# drone3.net
KiCad netlist of a schematic drawn in EAGLE
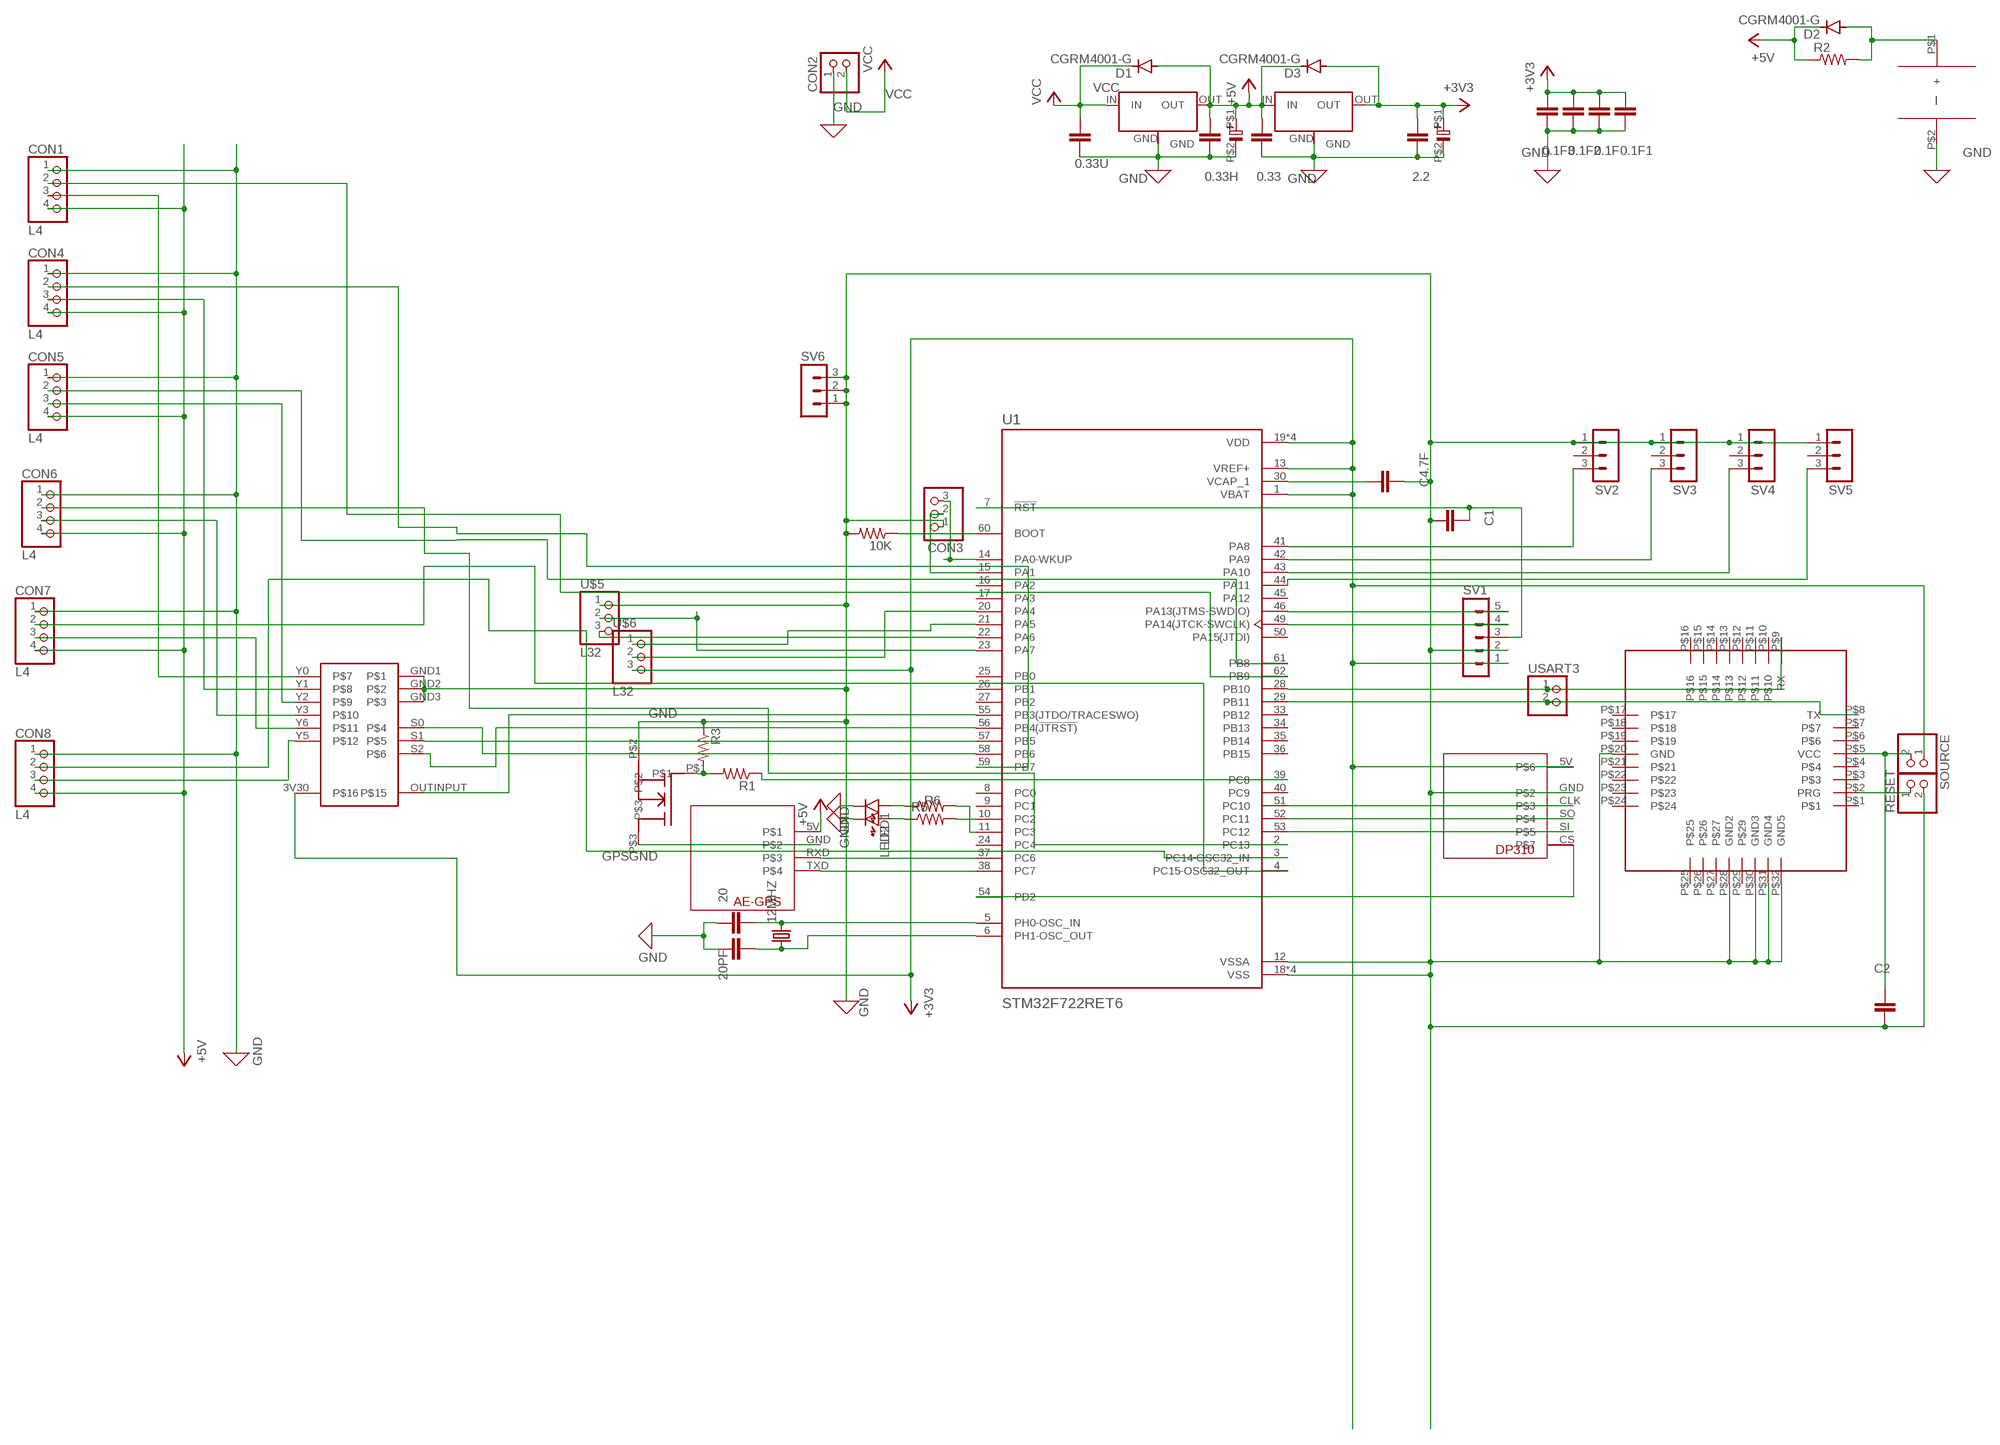
[diagram p0: schematic, sheet 1]

(export (version "E")
  (design (tool "Eeschema 10.0.6"))
  (components
    (comp (ref "0.1F")
      (value "C-EUC0603")
      (footprint "eagle-import:C0603")
      (libsource (lib "eagle-import") (part "C-EUC0603"))
    )
    (comp (ref "0.1F1")
      (value "C-EUC0603")
      (footprint "eagle-import:C0603")
      (libsource (lib "eagle-import") (part "C-EUC0603"))
    )
    (comp (ref "0.1F2")
      (value "C-EUC0603")
      (footprint "eagle-import:C0603")
      (libsource (lib "eagle-import") (part "C-EUC0603"))
    )
    (comp (ref "0.1F3")
      (value "C-EUC0603")
      (footprint "eagle-import:C0603")
      (libsource (lib "eagle-import") (part "C-EUC0603"))
    )
    (comp (ref "0.33")
      (value "C-EUC0603")
      (footprint "eagle-import:C0603")
      (libsource (lib "eagle-import") (part "C-EUC0603"))
    )
    (comp (ref "0.33H")
      (value "C-EUC0603")
      (footprint "eagle-import:C0603")
      (libsource (lib "eagle-import") (part "C-EUC0603"))
    )
    (comp (ref "0.33U")
      (value "C-EUC0603")
      (footprint "eagle-import:C0603")
      (libsource (lib "eagle-import") (part "C-EUC0603"))
    )
    (comp (ref "2.2")
      (value "C-EUC0603")
      (footprint "eagle-import:C0603")
      (libsource (lib "eagle-import") (part "C-EUC0603"))
    )
    (comp (ref "10K")
      (value "R-US_R0603")
      (footprint "eagle-import:R0603")
      (libsource (lib "eagle-import") (part "R-US_R0603"))
    )
    (comp (ref "12MHZ")
      (value "CRYSTALHC49S")
      (footprint "eagle-import:HC49_S")
      (fields (field (name "SPICEPREFIX") "B"))
      (libsource (lib "eagle-import") (part "CRYSTALHC49S"))
    )
    (comp (ref "20")
      (value "C-EUC0603")
      (footprint "eagle-import:C0603")
      (libsource (lib "eagle-import") (part "C-EUC0603"))
    )
    (comp (ref "20PF")
      (value "C-EUC0603")
      (footprint "eagle-import:C0603")
      (libsource (lib "eagle-import") (part "C-EUC0603"))
    )
    (comp (ref "47")
      (value "UCD0J470MCL1GS")
      (footprint "eagle-import:UCD0J470MCL1GS")
      (libsource (lib "eagle-import") (part "UCD0J470MCL1GS"))
    )
    (comp (ref "47U")
      (value "UCD0J470MCL1GS")
      (footprint "eagle-import:UCD0J470MCL1GS")
      (libsource (lib "eagle-import") (part "UCD0J470MCL1GS"))
    )
    (comp (ref "C1")
      (value "C-EUC0603")
      (footprint "eagle-import:C0603")
      (libsource (lib "eagle-import") (part "C-EUC0603"))
    )
    (comp (ref "C2")
      (value "C-EUC0603")
      (footprint "eagle-import:C0603")
      (libsource (lib "eagle-import") (part "C-EUC0603"))
    )
    (comp (ref "C4.7F")
      (value "C-EUC0603")
      (footprint "eagle-import:C0603")
      (libsource (lib "eagle-import") (part "C-EUC0603"))
    )
    (comp (ref "CON1")
      (value "L4")
      (footprint "eagle-import:L_4")
      (libsource (lib "eagle-import") (part "L4"))
    )
    (comp (ref "CON2")
      (value "L2")
      (footprint "eagle-import:L_2")
      (libsource (lib "eagle-import") (part "L2"))
    )
    (comp (ref "CON3")
      (value "L3")
      (footprint "eagle-import:L_3")
      (libsource (lib "eagle-import") (part "L3"))
    )
    (comp (ref "CON4")
      (value "L4")
      (footprint "eagle-import:L_4")
      (libsource (lib "eagle-import") (part "L4"))
    )
    (comp (ref "CON5")
      (value "L4")
      (footprint "eagle-import:L_4")
      (libsource (lib "eagle-import") (part "L4"))
    )
    (comp (ref "CON6")
      (value "L4")
      (footprint "eagle-import:L_4")
      (libsource (lib "eagle-import") (part "L4"))
    )
    (comp (ref "CON7")
      (value "L4")
      (footprint "eagle-import:L_4")
      (libsource (lib "eagle-import") (part "L4"))
    )
    (comp (ref "CON8")
      (value "L4")
      (footprint "eagle-import:L_4")
      (libsource (lib "eagle-import") (part "L4"))
    )
    (comp (ref "CS1")
      (value "DP310DP310")
      (footprint "eagle-import:AE-GPS-HOLE")
      (libsource (lib "eagle-import") (part "DP310DP310"))
    )
    (comp (ref "D1")
      (value "CGRM4001-G")
      (footprint "eagle-import:SOD-123_MINI-SMA")
      (libsource (lib "eagle-import") (part "CGRM400-G1"))
    )
    (comp (ref "D2")
      (value "CGRM4001-G")
      (footprint "eagle-import:SOD-123_MINI-SMA")
      (libsource (lib "eagle-import") (part "CGRM400-G1"))
    )
    (comp (ref "D3")
      (value "CGRM4001-G")
      (footprint "eagle-import:SOD-123_MINI-SMA")
      (libsource (lib "eagle-import") (part "CGRM400-G1"))
    )
    (comp (ref "LED1")
      (value "LED1608")
      (footprint "eagle-import:LED1608")
      (libsource (lib "eagle-import") (part "LED1608"))
    )
    (comp (ref "LED2")
      (value "LED1608")
      (footprint "eagle-import:LED1608")
      (libsource (lib "eagle-import") (part "LED1608"))
    )
    (comp (ref "OUTPUT")
      (value "MULTI")
      (footprint "eagle-import:MULTI")
      (libsource (lib "eagle-import") (part "MULTI"))
    )
    (comp (ref "R1")
      (value "R-US_R0603")
      (footprint "eagle-import:R0603")
      (libsource (lib "eagle-import") (part "R-US_R0603"))
    )
    (comp (ref "R2")
      (value "R-US_0207/7")
      (footprint "eagle-import:0207_7")
      (libsource (lib "eagle-import") (part "R-US_0207/7"))
    )
    (comp (ref "R3")
      (value "R-US_R0603")
      (footprint "eagle-import:R0603")
      (libsource (lib "eagle-import") (part "R-US_R0603"))
    )
    (comp (ref "R5")
      (value "R-US_R0603")
      (footprint "eagle-import:R0603")
      (libsource (lib "eagle-import") (part "R-US_R0603"))
    )
    (comp (ref "R6")
      (value "R-US_R0603")
      (footprint "eagle-import:R0603")
      (libsource (lib "eagle-import") (part "R-US_R0603"))
    )
    (comp (ref "RESET")
      (value "PINHD-1X2")
      (footprint "eagle-import:1X02")
      (libsource (lib "eagle-import") (part "PINHD-1X2"))
    )
    (comp (ref "SOURCE")
      (value "PINHD-1X2")
      (footprint "eagle-import:1X02")
      (libsource (lib "eagle-import") (part "PINHD-1X2"))
    )
    (comp (ref "SV1")
      (value "MA05-1")
      (footprint "eagle-import:MA05-1")
      (libsource (lib "eagle-import") (part "MA05-1"))
    )
    (comp (ref "SV2")
      (value "MA03-1")
      (footprint "eagle-import:MA03-1")
      (libsource (lib "eagle-import") (part "MA03-1"))
    )
    (comp (ref "SV3")
      (value "MA03-1")
      (footprint "eagle-import:MA03-1")
      (libsource (lib "eagle-import") (part "MA03-1"))
    )
    (comp (ref "SV4")
      (value "MA03-1")
      (footprint "eagle-import:MA03-1")
      (libsource (lib "eagle-import") (part "MA03-1"))
    )
    (comp (ref "SV5")
      (value "MA03-1")
      (footprint "eagle-import:MA03-1")
      (libsource (lib "eagle-import") (part "MA03-1"))
    )
    (comp (ref "SV6")
      (value "MA03-1")
      (footprint "eagle-import:MA03-1")
      (libsource (lib "eagle-import") (part "MA03-1"))
    )
    (comp (ref "U$1")
      (value "LITE")
      (footprint "eagle-import:LITE")
      (libsource (lib "eagle-import") (part "LITE"))
    )
    (comp (ref "U$3")
      (value "AE-GPS-HOLE")
      (footprint "eagle-import:AE-GPS-HOLE")
      (libsource (lib "eagle-import") (part "AE-GPS-HOLE"))
    )
    (comp (ref "U$4")
      (value "NJM2391DL1-33")
      (footprint "eagle-import:NJM2391DL1-33")
      (libsource (lib "eagle-import") (part "NJM2391DL1-33"))
    )
    (comp (ref "U$5")
      (value "L32")
      (footprint "eagle-import:L_32")
      (libsource (lib "eagle-import") (part "L32"))
    )
    (comp (ref "U$6")
      (value "L32")
      (footprint "eagle-import:L_32")
      (libsource (lib "eagle-import") (part "L32"))
    )
    (comp (ref "U$7")
      (value "SSM3K329R")
      (footprint "eagle-import:SSM3K329R")
      (libsource (lib "eagle-import") (part "SSM3K329R"))
    )
    (comp (ref "U$8")
      (value "VEC5R4355QG-I")
      (footprint "eagle-import:VEC5R4355QG-I")
      (libsource (lib "eagle-import") (part "VEC5R4355QG-I"))
    )
    (comp (ref "U$9")
      (value "NJM2391DL1-33")
      (footprint "eagle-import:NJM2391DL1-33")
      (libsource (lib "eagle-import") (part "NJM2391DL1-33"))
    )
    (comp (ref "U1")
      (value "STM32F722RET6")
      (footprint "eagle-import:QFP50P1200X1200X160-64N")
      (fields (field (name "MF") "STMicroelectronics"))
      (libsource (lib "eagle-import") (part "STM32F722RET6"))
    )
    (comp (ref "USART3")
      (value "PINHD-1X2")
      (footprint "eagle-import:1X02")
      (libsource (lib "eagle-import") (part "PINHD-1X2"))
    )
  )
  (nets
    (net (code "1") (name "+3V3") (class "Default")
      (node (ref "0.1F") (pin "1") (pinfunction "1_1") (pintype "passive"))
      (node (ref "0.1F1") (pin "1") (pinfunction "1_1") (pintype "passive"))
      (node (ref "0.1F2") (pin "1") (pinfunction "1_1") (pintype "passive"))
      (node (ref "0.1F3") (pin "1") (pinfunction "1_1") (pintype "passive"))
      (node (ref "2.2") (pin "1") (pinfunction "1_1") (pintype "passive"))
      (node (ref "47") (pin "P$1") (pinfunction "+_P$1") (pintype "bidirectional"))
      (node (ref "CS1") (pin "5V") (pinfunction "P$6_5V") (pintype "bidirectional"))
      (node (ref "D3") (pin "A") (pinfunction "A_A") (pintype "passive"))
      (node (ref "OUTPUT") (pin "3V30") (pinfunction "P$16_3V30") (pintype "bidirectional"))
      (node (ref "SOURCE") (pin "1") (pinfunction "1_1") (pintype "passive"))
      (node (ref "SV1") (pin "1") (pinfunction "1_1") (pintype "passive"))
      (node (ref "U$4") (pin "OUT") (pinfunction "OUT_OUT") (pintype "bidirectional"))
      (node (ref "U$6") (pin "3") (pinfunction "3_3") (pintype "passive"))
      (node (ref "U1") (pin "1") (pinfunction "VBAT_1") (pintype "power_in"))
      (node (ref "U1") (pin "13") (pinfunction "VREF+_13") (pintype "power_in"))
      (node (ref "U1") (pin "19") (pinfunction "VDD_19") (pintype "power_in"))
      (node (ref "U1") (pin "32") (pinfunction "VDD_32") (pintype "power_in"))
      (node (ref "U1") (pin "48") (pinfunction "VDD_48") (pintype "power_in"))
      (node (ref "U1") (pin "64") (pinfunction "VDD_64") (pintype "power_in"))
    )
    (net (code "2") (name "+5V") (class "Default")
      (node (ref "0.33") (pin "1") (pinfunction "1_1") (pintype "passive"))
      (node (ref "0.33H") (pin "1") (pinfunction "1_1") (pintype "passive"))
      (node (ref "47U") (pin "P$1") (pinfunction "+_P$1") (pintype "bidirectional"))
      (node (ref "CON1") (pin "4") (pinfunction "4_4") (pintype "passive"))
      (node (ref "CON4") (pin "4") (pinfunction "4_4") (pintype "passive"))
      (node (ref "CON5") (pin "4") (pinfunction "4_4") (pintype "passive"))
      (node (ref "CON6") (pin "4") (pinfunction "4_4") (pintype "passive"))
      (node (ref "CON7") (pin "4") (pinfunction "4_4") (pintype "passive"))
      (node (ref "CON8") (pin "4") (pinfunction "4_4") (pintype "passive"))
      (node (ref "D1") (pin "A") (pinfunction "A_A") (pintype "passive"))
      (node (ref "D2") (pin "C") (pinfunction "C_C") (pintype "passive"))
      (node (ref "D3") (pin "C") (pinfunction "C_C") (pintype "passive"))
      (node (ref "R2") (pin "1") (pinfunction "1_1") (pintype "passive"))
      (node (ref "U$3") (pin "5V") (pinfunction "P$1_5V") (pintype "bidirectional"))
      (node (ref "U$4") (pin "IN") (pinfunction "IN_IN") (pintype "bidirectional"))
      (node (ref "U$9") (pin "OUT") (pinfunction "OUT_OUT") (pintype "bidirectional"))
    )
    (net (code "3") (name "/GPSGND") (class "Default")
      (node (ref "U$3") (pin "GND") (pinfunction "P$2_GND") (pintype "bidirectional"))
      (node (ref "U$7") (pin "P$3") (pinfunction "P$3_P$3") (pintype "bidirectional"))
    )
    (net (code "4") (name "GND") (class "Default")
      (node (ref "0.1F") (pin "2") (pinfunction "2_2") (pintype "passive"))
      (node (ref "0.1F1") (pin "2") (pinfunction "2_2") (pintype "passive"))
      (node (ref "0.1F2") (pin "2") (pinfunction "2_2") (pintype "passive"))
      (node (ref "0.1F3") (pin "2") (pinfunction "2_2") (pintype "passive"))
      (node (ref "0.33") (pin "2") (pinfunction "2_2") (pintype "passive"))
      (node (ref "0.33H") (pin "2") (pinfunction "2_2") (pintype "passive"))
      (node (ref "0.33U") (pin "2") (pinfunction "2_2") (pintype "passive"))
      (node (ref "10K") (pin "2") (pinfunction "2_2") (pintype "passive"))
      (node (ref "2.2") (pin "2") (pinfunction "2_2") (pintype "passive"))
      (node (ref "20") (pin "1") (pinfunction "1_1") (pintype "passive"))
      (node (ref "20PF") (pin "1") (pinfunction "1_1") (pintype "passive"))
      (node (ref "47") (pin "P$2") (pinfunction "ー_P$2") (pintype "bidirectional"))
      (node (ref "47U") (pin "P$2") (pinfunction "ー_P$2") (pintype "bidirectional"))
      (node (ref "C1") (pin "1") (pinfunction "1_1") (pintype "passive"))
      (node (ref "C2") (pin "1") (pinfunction "1_1") (pintype "passive"))
      (node (ref "C4.7F") (pin "2") (pinfunction "2_2") (pintype "passive"))
      (node (ref "CON1") (pin "1") (pinfunction "1_1") (pintype "passive"))
      (node (ref "CON2") (pin "1") (pinfunction "1_1") (pintype "passive"))
      (node (ref "CON3") (pin "1") (pinfunction "1_1") (pintype "passive"))
      (node (ref "CON4") (pin "1") (pinfunction "1_1") (pintype "passive"))
      (node (ref "CON5") (pin "1") (pinfunction "1_1") (pintype "passive"))
      (node (ref "CON6") (pin "1") (pinfunction "1_1") (pintype "passive"))
      (node (ref "CON7") (pin "1") (pinfunction "1_1") (pintype "passive"))
      (node (ref "CON8") (pin "1") (pinfunction "1_1") (pintype "passive"))
      (node (ref "CS1") (pin "GND") (pinfunction "P$2_GND") (pintype "bidirectional"))
      (node (ref "LED1") (pin "K") (pinfunction "K_K") (pintype "passive"))
      (node (ref "LED2") (pin "K") (pinfunction "K_K") (pintype "passive"))
      (node (ref "OUTPUT") (pin "GND1") (pinfunction "P$1_GND1") (pintype "bidirectional"))
      (node (ref "OUTPUT") (pin "GND2") (pinfunction "P$2_GND2") (pintype "bidirectional"))
      (node (ref "OUTPUT") (pin "GND3") (pinfunction "P$3_GND3") (pintype "bidirectional"))
      (node (ref "R3") (pin "1") (pinfunction "1_1") (pintype "passive"))
      (node (ref "RESET") (pin "2") (pinfunction "2_2") (pintype "passive"))
      (node (ref "SV1") (pin "2") (pinfunction "2_2") (pintype "passive"))
      (node (ref "SV2") (pin "1") (pinfunction "1_1") (pintype "passive"))
      (node (ref "SV3") (pin "1") (pinfunction "1_1") (pintype "passive"))
      (node (ref "SV4") (pin "1") (pinfunction "1_1") (pintype "passive"))
      (node (ref "SV5") (pin "1") (pinfunction "1_1") (pintype "passive"))
      (node (ref "SV6") (pin "1") (pinfunction "1_1") (pintype "passive"))
      (node (ref "SV6") (pin "2") (pinfunction "2_2") (pintype "passive"))
      (node (ref "SV6") (pin "3") (pinfunction "3_3") (pintype "passive"))
      (node (ref "U$1") (pin "P$20") (pinfunction "GND_P$20") (pintype "bidirectional"))
      (node (ref "U$1") (pin "P$28") (pinfunction "GND2_P$28") (pintype "bidirectional"))
      (node (ref "U$1") (pin "P$30") (pinfunction "GND3_P$30") (pintype "bidirectional"))
      (node (ref "U$1") (pin "P$31") (pinfunction "GND4_P$31") (pintype "bidirectional"))
      (node (ref "U$1") (pin "P$32") (pinfunction "GND5_P$32") (pintype "bidirectional"))
      (node (ref "U$4") (pin "GND") (pinfunction "GND_GND") (pintype "bidirectional"))
      (node (ref "U$5") (pin "1") (pinfunction "1_1") (pintype "passive"))
      (node (ref "U$7") (pin "P$2") (pinfunction "P$2_P$2") (pintype "bidirectional"))
      (node (ref "U$8") (pin "P$2") (pinfunction "ー_P$2") (pintype "bidirectional"))
      (node (ref "U$9") (pin "GND") (pinfunction "GND_GND") (pintype "bidirectional"))
      (node (ref "U1") (pin "12") (pinfunction "VSSA_12") (pintype "power_in"))
      (node (ref "U1") (pin "18") (pinfunction "VSS_18") (pintype "power_in"))
      (node (ref "U1") (pin "31") (pinfunction "VSS_31") (pintype "power_in"))
      (node (ref "U1") (pin "47") (pinfunction "VSS_47") (pintype "power_in"))
      (node (ref "U1") (pin "63") (pinfunction "VSS_63") (pintype "power_in"))
    )
    (net (code "5") (name "Net-(CS1-P$3)") (class "Default")
      (node (ref "CS1") (pin "CLK") (pinfunction "P$3_CLK") (pintype "bidirectional"))
      (node (ref "U1") (pin "51") (pinfunction "PC10_51") (pintype "bidirectional"))
    )
    (net (code "6") (name "Net-(CS1-P$4)") (class "Default")
      (node (ref "CS1") (pin "SO") (pinfunction "P$4_SO") (pintype "bidirectional"))
      (node (ref "U1") (pin "52") (pinfunction "PC11_52") (pintype "bidirectional"))
    )
    (net (code "7") (name "Net-(CS1-P$5)") (class "Default")
      (node (ref "CS1") (pin "SI") (pinfunction "P$5_SI") (pintype "bidirectional"))
      (node (ref "U1") (pin "53") (pinfunction "PC12_53") (pintype "bidirectional"))
    )
    (net (code "8") (name "Net-(CS1-P$7)") (class "Default")
      (node (ref "CS1") (pin "CS") (pinfunction "P$7_CS") (pintype "bidirectional"))
      (node (ref "U1") (pin "54") (pinfunction "PD2_54") (pintype "bidirectional"))
    )
    (net (code "9") (name "Net-(LED1-PadA)") (class "Default")
      (node (ref "LED1") (pin "A") (pinfunction "A_A") (pintype "passive"))
      (node (ref "R6") (pin "1") (pinfunction "1_1") (pintype "passive"))
    )
    (net (code "10") (name "Net-(LED2-PadA)") (class "Default")
      (node (ref "LED2") (pin "A") (pinfunction "A_A") (pintype "passive"))
      (node (ref "R5") (pin "1") (pinfunction "1_1") (pintype "passive"))
    )
    (net (code "11") (name "Net-(OUTPUT-P$4)") (class "Default")
      (node (ref "OUTPUT") (pin "S0") (pinfunction "P$4_S0") (pintype "bidirectional"))
      (node (ref "U1") (pin "58") (pinfunction "PB6_58") (pintype "bidirectional"))
    )
    (net (code "12") (name "Net-(OUTPUT-P$5)") (class "Default")
      (node (ref "OUTPUT") (pin "S1") (pinfunction "P$5_S1") (pintype "bidirectional"))
      (node (ref "U1") (pin "57") (pinfunction "PB5_57") (pintype "bidirectional"))
    )
    (net (code "13") (name "Net-(OUTPUT-P$6)") (class "Default")
      (node (ref "OUTPUT") (pin "S2") (pinfunction "P$6_S2") (pintype "bidirectional"))
      (node (ref "U1") (pin "56") (pinfunction "PB4(~{JTRST})_56") (pintype "bidirectional"))
    )
    (net (code "14") (name "Net-(OUTPUT-P$7)") (class "Default")
      (node (ref "CON1") (pin "3") (pinfunction "3_3") (pintype "passive"))
      (node (ref "OUTPUT") (pin "Y0") (pinfunction "P$7_Y0") (pintype "bidirectional"))
    )
    (net (code "15") (name "Net-(OUTPUT-P$8)") (class "Default")
      (node (ref "CON4") (pin "3") (pinfunction "3_3") (pintype "passive"))
      (node (ref "OUTPUT") (pin "Y1") (pinfunction "P$8_Y1") (pintype "bidirectional"))
    )
    (net (code "16") (name "Net-(OUTPUT-P$9)") (class "Default")
      (node (ref "CON5") (pin "3") (pinfunction "3_3") (pintype "passive"))
      (node (ref "OUTPUT") (pin "Y2") (pinfunction "P$9_Y2") (pintype "bidirectional"))
    )
    (net (code "17") (name "Net-(OUTPUT-P$10)") (class "Default")
      (node (ref "CON6") (pin "3") (pinfunction "3_3") (pintype "passive"))
      (node (ref "OUTPUT") (pin "Y3") (pinfunction "P$10_Y3") (pintype "bidirectional"))
    )
    (net (code "18") (name "Net-(OUTPUT-P$11)") (class "Default")
      (node (ref "CON7") (pin "3") (pinfunction "3_3") (pintype "passive"))
      (node (ref "OUTPUT") (pin "Y6") (pinfunction "P$11_Y6") (pintype "bidirectional"))
    )
    (net (code "19") (name "Net-(OUTPUT-P$12)") (class "Default")
      (node (ref "CON8") (pin "3") (pinfunction "3_3") (pintype "passive"))
      (node (ref "OUTPUT") (pin "Y5") (pinfunction "P$12_Y5") (pintype "bidirectional"))
    )
    (net (code "20") (name "Net-(OUTPUT-P$15)") (class "Default")
      (node (ref "OUTPUT") (pin "OUTINPUT") (pinfunction "P$15_OUTINPUT") (pintype "bidirectional"))
      (node (ref "U1") (pin "55") (pinfunction "PB3(JTDO/TRACESWO)_55") (pintype "bidirectional"))
    )
    (net (code "21") (name "Net-(R1-Pad2)") (class "Default")
      (node (ref "R1") (pin "2") (pinfunction "2_2") (pintype "passive"))
      (node (ref "R3") (pin "2") (pinfunction "2_2") (pintype "passive"))
      (node (ref "U$7") (pin "P$1") (pinfunction "P$1_P$1") (pintype "bidirectional"))
    )
    (net (code "22") (name "Net-(U$1-PRG)") (class "Default")
      (node (ref "RESET") (pin "1") (pinfunction "1_1") (pintype "passive"))
      (node (ref "U$1") (pin "P$2") (pinfunction "PRG_P$2") (pintype "bidirectional"))
    )
    (net (code "23") (name "Net-(U$1-RX)") (class "Default")
      (node (ref "U$1") (pin "P$9") (pinfunction "RX_P$9") (pintype "bidirectional"))
      (node (ref "U1") (pin "28") (pinfunction "PB10_28") (pintype "bidirectional"))
      (node (ref "USART3") (pin "1") (pinfunction "1_1") (pintype "passive"))
    )
    (net (code "24") (name "Net-(U$1-TX)") (class "Default")
      (node (ref "U$1") (pin "P$8") (pinfunction "TX_P$8") (pintype "bidirectional"))
      (node (ref "U1") (pin "29") (pinfunction "PB11_29") (pintype "bidirectional"))
      (node (ref "USART3") (pin "2") (pinfunction "2_2") (pintype "passive"))
    )
    (net (code "25") (name "Net-(U$1-VCC)") (class "Default")
      (node (ref "C2") (pin "2") (pinfunction "2_2") (pintype "passive"))
      (node (ref "SOURCE") (pin "2") (pinfunction "2_2") (pintype "passive"))
      (node (ref "U$1") (pin "P$5") (pinfunction "VCC_P$5") (pintype "bidirectional"))
    )
    (net (code "26") (name "Net-(U$3-P$3)") (class "Default")
      (node (ref "U$3") (pin "RXD") (pinfunction "P$3_RXD") (pintype "bidirectional"))
      (node (ref "U1") (pin "37") (pinfunction "PC6_37") (pintype "bidirectional"))
    )
    (net (code "27") (name "Net-(U$3-P$4)") (class "Default")
      (node (ref "U$3") (pin "TXD") (pinfunction "P$4_TXD") (pintype "bidirectional"))
      (node (ref "U1") (pin "38") (pinfunction "PC7_38") (pintype "bidirectional"))
    )
    (net (code "28") (name "Net-(U$8-+)") (class "Default")
      (node (ref "D2") (pin "A") (pinfunction "A_A") (pintype "passive"))
      (node (ref "R2") (pin "2") (pinfunction "2_2") (pintype "passive"))
      (node (ref "U$8") (pin "P$1") (pinfunction "+_P$1") (pintype "bidirectional"))
    )
    (net (code "29") (name "Net-(U1-BOOT)") (class "Default")
      (node (ref "10K") (pin "1") (pinfunction "1_1") (pintype "passive"))
      (node (ref "U1") (pin "60") (pinfunction "BOOT_60") (pintype "bidirectional"))
    )
    (net (code "30") (name "Net-(U1-PA0-WKUP)") (class "Default")
      (node (ref "CON3") (pin "3") (pinfunction "3_3") (pintype "passive"))
      (node (ref "U1") (pin "14") (pinfunction "PA0-WKUP_14") (pintype "bidirectional"))
    )
    (net (code "31") (name "Net-(U1-PA1)") (class "Default")
      (node (ref "CON3") (pin "2") (pinfunction "2_2") (pintype "passive"))
      (node (ref "U1") (pin "15") (pinfunction "PA1_15") (pintype "bidirectional"))
    )
    (net (code "32") (name "Net-(U1-PA4)") (class "Default")
      (node (ref "U$6") (pin "2") (pinfunction "2_2") (pintype "passive"))
      (node (ref "U1") (pin "20") (pinfunction "PA4_20") (pintype "bidirectional"))
    )
    (net (code "33") (name "Net-(U1-PA5)") (class "Default")
      (node (ref "U$6") (pin "1") (pinfunction "1_1") (pintype "passive"))
      (node (ref "U1") (pin "21") (pinfunction "PA5_21") (pintype "bidirectional"))
    )
    (net (code "34") (name "Net-(U1-PA6)") (class "Default")
      (node (ref "U$5") (pin "3") (pinfunction "3_3") (pintype "passive"))
      (node (ref "U1") (pin "22") (pinfunction "PA6_22") (pintype "bidirectional"))
    )
    (net (code "35") (name "Net-(U1-PA7)") (class "Default")
      (node (ref "U$5") (pin "2") (pinfunction "2_2") (pintype "passive"))
      (node (ref "U1") (pin "23") (pinfunction "PA7_23") (pintype "bidirectional"))
    )
    (net (code "36") (name "Net-(U1-PA8)") (class "Default")
      (node (ref "SV2") (pin "3") (pinfunction "3_3") (pintype "passive"))
      (node (ref "U1") (pin "41") (pinfunction "PA8_41") (pintype "bidirectional"))
    )
    (net (code "37") (name "Net-(U1-PA9)") (class "Default")
      (node (ref "SV3") (pin "3") (pinfunction "3_3") (pintype "passive"))
      (node (ref "U1") (pin "42") (pinfunction "PA9_42") (pintype "bidirectional"))
    )
    (net (code "38") (name "Net-(U1-PA10)") (class "Default")
      (node (ref "SV4") (pin "3") (pinfunction "3_3") (pintype "passive"))
      (node (ref "U1") (pin "43") (pinfunction "PA10_43") (pintype "bidirectional"))
    )
    (net (code "39") (name "Net-(U1-PA11)") (class "Default")
      (node (ref "SV5") (pin "3") (pinfunction "3_3") (pintype "passive"))
      (node (ref "U1") (pin "44") (pinfunction "PA11_44") (pintype "bidirectional"))
    )
    (net (code "40") (name "Net-(U1-PA13(JTMS-SWDIO))") (class "Default")
      (node (ref "SV1") (pin "5") (pinfunction "5_5") (pintype "passive"))
      (node (ref "U1") (pin "46") (pinfunction "PA13(JTMS-SWDIO)_46") (pintype "bidirectional"))
    )
    (net (code "41") (name "Net-(U1-PA14(JTCK-SWCLK))") (class "Default")
      (node (ref "SV1") (pin "4") (pinfunction "4_4") (pintype "passive"))
      (node (ref "U1") (pin "49") (pinfunction "PA14(JTCK-SWCLK)_49") (pintype "bidirectional"))
    )
    (net (code "42") (name "Net-(U1-PB7)") (class "Default")
      (node (ref "CON4") (pin "2") (pinfunction "2_2") (pintype "passive"))
      (node (ref "U1") (pin "59") (pinfunction "PB7_59") (pintype "bidirectional"))
    )
    (net (code "43") (name "Net-(U1-PB8)") (class "Default")
      (node (ref "CON5") (pin "2") (pinfunction "2_2") (pintype "passive"))
      (node (ref "U1") (pin "61") (pinfunction "PB8_61") (pintype "bidirectional"))
    )
    (net (code "44") (name "Net-(U1-PB9)") (class "Default")
      (node (ref "CON1") (pin "2") (pinfunction "2_2") (pintype "passive"))
      (node (ref "U1") (pin "62") (pinfunction "PB9_62") (pintype "bidirectional"))
    )
    (net (code "45") (name "Net-(U1-PC2)") (class "Default")
      (node (ref "R5") (pin "2") (pinfunction "2_2") (pintype "passive"))
      (node (ref "U1") (pin "10") (pinfunction "PC2_10") (pintype "bidirectional"))
    )
    (net (code "46") (name "Net-(U1-PC3)") (class "Default")
      (node (ref "R6") (pin "2") (pinfunction "2_2") (pintype "passive"))
      (node (ref "U1") (pin "11") (pinfunction "PC3_11") (pintype "bidirectional"))
    )
    (net (code "47") (name "Net-(U1-PC8)") (class "Default")
      (node (ref "R1") (pin "1") (pinfunction "1_1") (pintype "passive"))
      (node (ref "U1") (pin "39") (pinfunction "PC8_39") (pintype "bidirectional"))
    )
    (net (code "48") (name "Net-(U1-PC13)") (class "Default")
      (node (ref "CON6") (pin "2") (pinfunction "2_2") (pintype "passive"))
      (node (ref "U1") (pin "2") (pinfunction "PC13_2") (pintype "bidirectional"))
    )
    (net (code "49") (name "Net-(U1-PC14-OSC32_IN)") (class "Default")
      (node (ref "CON8") (pin "2") (pinfunction "2_2") (pintype "passive"))
      (node (ref "U1") (pin "3") (pinfunction "PC14-OSC32_IN_3") (pintype "bidirectional"))
    )
    (net (code "50") (name "Net-(U1-PC15-OSC32_OUT)") (class "Default")
      (node (ref "CON7") (pin "2") (pinfunction "2_2") (pintype "passive"))
      (node (ref "U1") (pin "4") (pinfunction "PC15-OSC32_OUT_4") (pintype "bidirectional"))
    )
    (net (code "51") (name "Net-(U1-PH0-OSC_IN)") (class "Default")
      (node (ref "12MHZ") (pin "2") (pinfunction "2_2") (pintype "passive"))
      (node (ref "20") (pin "2") (pinfunction "2_2") (pintype "passive"))
      (node (ref "U1") (pin "5") (pinfunction "PH0-OSC_IN_5") (pintype "bidirectional"))
    )
    (net (code "52") (name "Net-(U1-PH1-OSC_OUT)") (class "Default")
      (node (ref "12MHZ") (pin "1") (pinfunction "1_1") (pintype "passive"))
      (node (ref "20PF") (pin "2") (pinfunction "2_2") (pintype "passive"))
      (node (ref "U1") (pin "6") (pinfunction "PH1-OSC_OUT_6") (pintype "bidirectional"))
    )
    (net (code "53") (name "Net-(U1-VCAP_1)") (class "Default")
      (node (ref "C4.7F") (pin "1") (pinfunction "1_1") (pintype "passive"))
      (node (ref "U1") (pin "30") (pinfunction "VCAP_1_30") (pintype "power_in"))
    )
    (net (code "54") (name "Net-(U1-~{RST})") (class "Default")
      (node (ref "C1") (pin "2") (pinfunction "2_2") (pintype "passive"))
      (node (ref "SV1") (pin "3") (pinfunction "3_3") (pintype "passive"))
      (node (ref "U1") (pin "7") (pinfunction "~{RST}_7") (pintype "input"))
    )
    (net (code "55") (name "VCC") (class "Default")
      (node (ref "0.33U") (pin "1") (pinfunction "1_1") (pintype "passive"))
      (node (ref "CON2") (pin "2") (pinfunction "2_2") (pintype "passive"))
      (node (ref "D1") (pin "C") (pinfunction "C_C") (pintype "passive"))
      (node (ref "U$9") (pin "IN") (pinfunction "IN_IN") (pintype "bidirectional"))
    )
    (net (code "56") (name "unconnected-(SV2-Pad2)") (class "Default")
      (node (ref "SV2") (pin "2") (pinfunction "2_2") (pintype "passive"))
    )
    (net (code "57") (name "unconnected-(SV3-Pad2)") (class "Default")
      (node (ref "SV3") (pin "2") (pinfunction "2_2") (pintype "passive"))
    )
    (net (code "58") (name "unconnected-(SV4-Pad2)") (class "Default")
      (node (ref "SV4") (pin "2") (pinfunction "2_2") (pintype "passive"))
    )
    (net (code "59") (name "unconnected-(SV5-Pad2)") (class "Default")
      (node (ref "SV5") (pin "2") (pinfunction "2_2") (pintype "passive"))
    )
    (net (code "60") (name "unconnected-(U$1-PadP$1)") (class "Default")
      (node (ref "U$1") (pin "P$1") (pinfunction "P$1_P$1") (pintype "bidirectional"))
    )
    (net (code "61") (name "unconnected-(U$1-PadP$3)") (class "Default")
      (node (ref "U$1") (pin "P$3") (pinfunction "P$3_P$3") (pintype "bidirectional"))
    )
    (net (code "62") (name "unconnected-(U$1-PadP$4)") (class "Default")
      (node (ref "U$1") (pin "P$4") (pinfunction "P$4_P$4") (pintype "bidirectional"))
    )
    (net (code "63") (name "unconnected-(U$1-PadP$6)") (class "Default")
      (node (ref "U$1") (pin "P$6") (pinfunction "P$6_P$6") (pintype "bidirectional"))
    )
    (net (code "64") (name "unconnected-(U$1-PadP$7)") (class "Default")
      (node (ref "U$1") (pin "P$7") (pinfunction "P$7_P$7") (pintype "bidirectional"))
    )
    (net (code "65") (name "unconnected-(U$1-PadP$10)") (class "Default")
      (node (ref "U$1") (pin "P$10") (pinfunction "P$10_P$10") (pintype "bidirectional"))
    )
    (net (code "66") (name "unconnected-(U$1-PadP$11)") (class "Default")
      (node (ref "U$1") (pin "P$11") (pinfunction "P$11_P$11") (pintype "bidirectional"))
    )
    (net (code "67") (name "unconnected-(U$1-PadP$12)") (class "Default")
      (node (ref "U$1") (pin "P$12") (pinfunction "P$12_P$12") (pintype "bidirectional"))
    )
    (net (code "68") (name "unconnected-(U$1-PadP$13)") (class "Default")
      (node (ref "U$1") (pin "P$13") (pinfunction "P$13_P$13") (pintype "bidirectional"))
    )
    (net (code "69") (name "unconnected-(U$1-PadP$14)") (class "Default")
      (node (ref "U$1") (pin "P$14") (pinfunction "P$14_P$14") (pintype "bidirectional"))
    )
    (net (code "70") (name "unconnected-(U$1-PadP$15)") (class "Default")
      (node (ref "U$1") (pin "P$15") (pinfunction "P$15_P$15") (pintype "bidirectional"))
    )
    (net (code "71") (name "unconnected-(U$1-PadP$16)") (class "Default")
      (node (ref "U$1") (pin "P$16") (pinfunction "P$16_P$16") (pintype "bidirectional"))
    )
    (net (code "72") (name "unconnected-(U$1-PadP$17)") (class "Default")
      (node (ref "U$1") (pin "P$17") (pinfunction "P$17_P$17") (pintype "bidirectional"))
    )
    (net (code "73") (name "unconnected-(U$1-PadP$18)") (class "Default")
      (node (ref "U$1") (pin "P$18") (pinfunction "P$18_P$18") (pintype "bidirectional"))
    )
    (net (code "74") (name "unconnected-(U$1-PadP$19)") (class "Default")
      (node (ref "U$1") (pin "P$19") (pinfunction "P$19_P$19") (pintype "bidirectional"))
    )
    (net (code "75") (name "unconnected-(U$1-PadP$21)") (class "Default")
      (node (ref "U$1") (pin "P$21") (pinfunction "P$21_P$21") (pintype "bidirectional"))
    )
    (net (code "76") (name "unconnected-(U$1-PadP$22)") (class "Default")
      (node (ref "U$1") (pin "P$22") (pinfunction "P$22_P$22") (pintype "bidirectional"))
    )
    (net (code "77") (name "unconnected-(U$1-PadP$23)") (class "Default")
      (node (ref "U$1") (pin "P$23") (pinfunction "P$23_P$23") (pintype "bidirectional"))
    )
    (net (code "78") (name "unconnected-(U$1-PadP$24)") (class "Default")
      (node (ref "U$1") (pin "P$24") (pinfunction "P$24_P$24") (pintype "bidirectional"))
    )
    (net (code "79") (name "unconnected-(U$1-PadP$25)") (class "Default")
      (node (ref "U$1") (pin "P$25") (pinfunction "P$25_P$25") (pintype "bidirectional"))
    )
    (net (code "80") (name "unconnected-(U$1-PadP$26)") (class "Default")
      (node (ref "U$1") (pin "P$26") (pinfunction "P$26_P$26") (pintype "bidirectional"))
    )
    (net (code "81") (name "unconnected-(U$1-PadP$27)") (class "Default")
      (node (ref "U$1") (pin "P$27") (pinfunction "P$27_P$27") (pintype "bidirectional"))
    )
    (net (code "82") (name "unconnected-(U$1-PadP$29)") (class "Default")
      (node (ref "U$1") (pin "P$29") (pinfunction "P$29_P$29") (pintype "bidirectional"))
    )
    (net (code "83") (name "unconnected-(U1-PA2-Pad16)") (class "Default")
      (node (ref "U1") (pin "16") (pinfunction "PA2_16") (pintype "bidirectional"))
    )
    (net (code "84") (name "unconnected-(U1-PA3-Pad17)") (class "Default")
      (node (ref "U1") (pin "17") (pinfunction "PA3_17") (pintype "bidirectional"))
    )
    (net (code "85") (name "unconnected-(U1-PA12-Pad45)") (class "Default")
      (node (ref "U1") (pin "45") (pinfunction "PA12_45") (pintype "bidirectional"))
    )
    (net (code "86") (name "unconnected-(U1-PA15(JTDI)-Pad50)") (class "Default")
      (node (ref "U1") (pin "50") (pinfunction "PA15(JTDI)_50") (pintype "bidirectional"))
    )
    (net (code "87") (name "unconnected-(U1-PB0-Pad25)") (class "Default")
      (node (ref "U1") (pin "25") (pinfunction "PB0_25") (pintype "bidirectional"))
    )
    (net (code "88") (name "unconnected-(U1-PB1-Pad26)") (class "Default")
      (node (ref "U1") (pin "26") (pinfunction "PB1_26") (pintype "bidirectional"))
    )
    (net (code "89") (name "unconnected-(U1-PB2-Pad27)") (class "Default")
      (node (ref "U1") (pin "27") (pinfunction "PB2_27") (pintype "bidirectional"))
    )
    (net (code "90") (name "unconnected-(U1-PB12-Pad33)") (class "Default")
      (node (ref "U1") (pin "33") (pinfunction "PB12_33") (pintype "bidirectional"))
    )
    (net (code "91") (name "unconnected-(U1-PB13-Pad34)") (class "Default")
      (node (ref "U1") (pin "34") (pinfunction "PB13_34") (pintype "bidirectional"))
    )
    (net (code "92") (name "unconnected-(U1-PB14-Pad35)") (class "Default")
      (node (ref "U1") (pin "35") (pinfunction "PB14_35") (pintype "bidirectional"))
    )
    (net (code "93") (name "unconnected-(U1-PB15-Pad36)") (class "Default")
      (node (ref "U1") (pin "36") (pinfunction "PB15_36") (pintype "bidirectional"))
    )
    (net (code "94") (name "unconnected-(U1-PC0-Pad8)") (class "Default")
      (node (ref "U1") (pin "8") (pinfunction "PC0_8") (pintype "bidirectional"))
    )
    (net (code "95") (name "unconnected-(U1-PC1-Pad9)") (class "Default")
      (node (ref "U1") (pin "9") (pinfunction "PC1_9") (pintype "bidirectional"))
    )
    (net (code "96") (name "unconnected-(U1-PC4-Pad24)") (class "Default")
      (node (ref "U1") (pin "24") (pinfunction "PC4_24") (pintype "bidirectional"))
    )
    (net (code "97") (name "unconnected-(U1-PC9-Pad40)") (class "Default")
      (node (ref "U1") (pin "40") (pinfunction "PC9_40") (pintype "bidirectional"))
    )
  )
)
